# power_stage.net
KiCad netlist of a schematic drawn in EAGLE
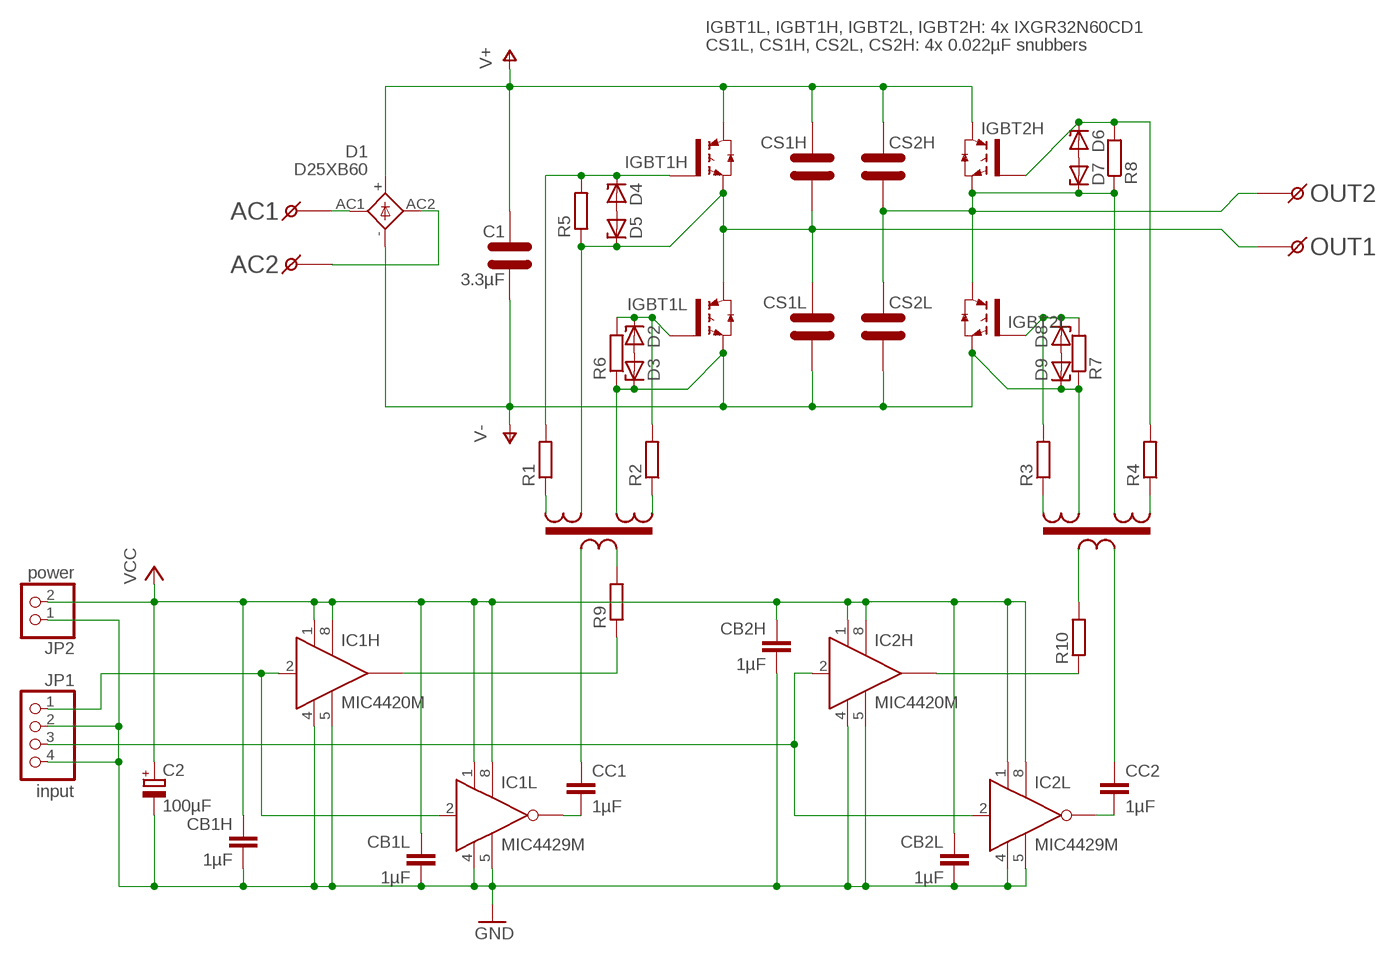
[diagram p0: schematic, sheet 1]

(export (version "E")
  (design (tool "Eeschema 10.0.6"))
  (components
    (comp (ref "C1")
      (value "3.3µF")
      (footprint "eagle-import:R75")
      (libsource (lib "eagle-import") (part "C_R75"))
    )
    (comp (ref "C2")
      (value "100µF")
      (footprint "eagle-import:E2,5-7")
      (libsource (lib "eagle-import") (part "CPOL-EUE2.5-7"))
    )
    (comp (ref "CB1H")
      (value "1µF")
      (footprint "eagle-import:C0805")
      (libsource (lib "eagle-import") (part "C-EUC0805"))
    )
    (comp (ref "CB1L")
      (value "1µF")
      (footprint "eagle-import:C0805")
      (libsource (lib "eagle-import") (part "C-EUC0805"))
    )
    (comp (ref "CB2H")
      (value "1µF")
      (footprint "eagle-import:C0805")
      (libsource (lib "eagle-import") (part "C-EUC0805"))
    )
    (comp (ref "CB2L")
      (value "1µF")
      (footprint "eagle-import:C0805")
      (libsource (lib "eagle-import") (part "C-EUC0805"))
    )
    (comp (ref "CC1")
      (value "1µF")
      (footprint "eagle-import:C0805")
      (libsource (lib "eagle-import") (part "C-EUC0805"))
    )
    (comp (ref "CC2")
      (value "1µF")
      (footprint "eagle-import:C0805")
      (libsource (lib "eagle-import") (part "C-EUC0805"))
    )
    (comp (ref "CS1H")
      (value "C_R76")
      (footprint "eagle-import:R76")
      (libsource (lib "eagle-import") (part "C_R76"))
    )
    (comp (ref "CS1L")
      (value "C_R76")
      (footprint "eagle-import:R76")
      (libsource (lib "eagle-import") (part "C_R76"))
    )
    (comp (ref "CS2H")
      (value "C_R76")
      (footprint "eagle-import:R76")
      (libsource (lib "eagle-import") (part "C_R76"))
    )
    (comp (ref "CS2L")
      (value "C_R76")
      (footprint "eagle-import:R76")
      (libsource (lib "eagle-import") (part "C_R76"))
    )
    (comp (ref "D1")
      (value "D25XB60")
      (footprint "eagle-import:D25XB60")
      (libsource (lib "eagle-import") (part "D25XB60"))
    )
    (comp (ref "D2")
      (value "ZENER-DIODESOD80C")
      (footprint "eagle-import:SOD80C")
      (libsource (lib "eagle-import") (part "ZENER-DIODESOD80C"))
    )
    (comp (ref "D3")
      (value "ZENER-DIODESOD80C")
      (footprint "eagle-import:SOD80C")
      (libsource (lib "eagle-import") (part "ZENER-DIODESOD80C"))
    )
    (comp (ref "D4")
      (value "ZENER-DIODESOD80C")
      (footprint "eagle-import:SOD80C")
      (libsource (lib "eagle-import") (part "ZENER-DIODESOD80C"))
    )
    (comp (ref "D5")
      (value "ZENER-DIODESOD80C")
      (footprint "eagle-import:SOD80C")
      (libsource (lib "eagle-import") (part "ZENER-DIODESOD80C"))
    )
    (comp (ref "D6")
      (value "ZENER-DIODESOD80C")
      (footprint "eagle-import:SOD80C")
      (libsource (lib "eagle-import") (part "ZENER-DIODESOD80C"))
    )
    (comp (ref "D7")
      (value "ZENER-DIODESOD80C")
      (footprint "eagle-import:SOD80C")
      (libsource (lib "eagle-import") (part "ZENER-DIODESOD80C"))
    )
    (comp (ref "D8")
      (value "ZENER-DIODESOD80C")
      (footprint "eagle-import:SOD80C")
      (libsource (lib "eagle-import") (part "ZENER-DIODESOD80C"))
    )
    (comp (ref "D9")
      (value "ZENER-DIODESOD80C")
      (footprint "eagle-import:SOD80C")
      (libsource (lib "eagle-import") (part "ZENER-DIODESOD80C"))
    )
    (comp (ref "GDT1")
      (value "GDT")
      (footprint "eagle-import:GDT")
      (libsource (lib "eagle-import") (part "GDT"))
    )
    (comp (ref "GDT2")
      (value "GDT")
      (footprint "eagle-import:GDT")
      (libsource (lib "eagle-import") (part "GDT"))
    )
    (comp (ref "IC1H")
      (value "MIC4420M")
      (footprint "eagle-import:SO-08")
      (libsource (lib "eagle-import") (part "MIC4420M"))
    )
    (comp (ref "IC1L")
      (value "MIC4429M")
      (footprint "eagle-import:SO-08")
      (libsource (lib "eagle-import") (part "MIC4429M"))
    )
    (comp (ref "IC2H")
      (value "MIC4420M")
      (footprint "eagle-import:SO-08")
      (libsource (lib "eagle-import") (part "MIC4420M"))
    )
    (comp (ref "IC2L")
      (value "MIC4429M")
      (footprint "eagle-import:SO-08")
      (libsource (lib "eagle-import") (part "MIC4429M"))
    )
    (comp (ref "IGBT1H")
      (value "IXGR32N60CD1")
      (footprint "eagle-import:TO-247AD-V")
      (libsource (lib "eagle-import") (part "IXGR32N60CD1"))
    )
    (comp (ref "IGBT1L")
      (value "IXGR32N60CD1")
      (footprint "eagle-import:TO-247AD-V")
      (libsource (lib "eagle-import") (part "IXGR32N60CD1"))
    )
    (comp (ref "IGBT2H")
      (value "IXGR32N60CD1")
      (footprint "eagle-import:TO-247AD-V")
      (libsource (lib "eagle-import") (part "IXGR32N60CD1"))
    )
    (comp (ref "IGBT2L")
      (value "IXGR32N60CD1")
      (footprint "eagle-import:TO-247AD-V")
      (libsource (lib "eagle-import") (part "IXGR32N60CD1"))
    )
    (comp (ref "J1")
      (value "AC1")
      (footprint "eagle-import:SCREW")
      (libsource (lib "eagle-import") (part "SCREW"))
    )
    (comp (ref "J2")
      (value "AC2")
      (footprint "eagle-import:SCREW")
      (libsource (lib "eagle-import") (part "SCREW"))
    )
    (comp (ref "J3")
      (value "OUT1")
      (footprint "eagle-import:SCREW")
      (libsource (lib "eagle-import") (part "SCREW"))
    )
    (comp (ref "J4")
      (value "OUT2")
      (footprint "eagle-import:SCREW")
      (libsource (lib "eagle-import") (part "SCREW"))
    )
    (comp (ref "JP1")
      (value "input")
      (footprint "eagle-import:1X04")
      (libsource (lib "eagle-import") (part "PINHD-1X4"))
    )
    (comp (ref "JP2")
      (value "power")
      (footprint "eagle-import:1X02")
      (libsource (lib "eagle-import") (part "PINHD-1X2"))
    )
    (comp (ref "R1")
      (value "R-EU_R0805")
      (footprint "eagle-import:R0805")
      (libsource (lib "eagle-import") (part "R-EU_R0805"))
    )
    (comp (ref "R2")
      (value "R-EU_R0805")
      (footprint "eagle-import:R0805")
      (libsource (lib "eagle-import") (part "R-EU_R0805"))
    )
    (comp (ref "R3")
      (value "R-EU_R0805")
      (footprint "eagle-import:R0805")
      (libsource (lib "eagle-import") (part "R-EU_R0805"))
    )
    (comp (ref "R4")
      (value "R-EU_R0805")
      (footprint "eagle-import:R0805")
      (libsource (lib "eagle-import") (part "R-EU_R0805"))
    )
    (comp (ref "R5")
      (value "R-EU_R0805")
      (footprint "eagle-import:R0805")
      (libsource (lib "eagle-import") (part "R-EU_R0805"))
    )
    (comp (ref "R6")
      (value "R-EU_R0805")
      (footprint "eagle-import:R0805")
      (libsource (lib "eagle-import") (part "R-EU_R0805"))
    )
    (comp (ref "R7")
      (value "R-EU_R0805")
      (footprint "eagle-import:R0805")
      (libsource (lib "eagle-import") (part "R-EU_R0805"))
    )
    (comp (ref "R8")
      (value "R-EU_R0805")
      (footprint "eagle-import:R0805")
      (libsource (lib "eagle-import") (part "R-EU_R0805"))
    )
    (comp (ref "R9")
      (value "R-EU_R0805")
      (footprint "eagle-import:R0805")
      (libsource (lib "eagle-import") (part "R-EU_R0805"))
    )
    (comp (ref "R10")
      (value "R-EU_R0805")
      (footprint "eagle-import:R0805")
      (libsource (lib "eagle-import") (part "R-EU_R0805"))
    )
  )
  (nets
    (net (code "1") (name "GND") (class "Default")
      (node (ref "C2") (pin "-") (pinfunction "-_-") (pintype "passive"))
      (node (ref "CB1H") (pin "2") (pinfunction "2_2") (pintype "passive"))
      (node (ref "CB1L") (pin "2") (pinfunction "2_2") (pintype "passive"))
      (node (ref "CB2H") (pin "2") (pinfunction "2_2") (pintype "passive"))
      (node (ref "CB2L") (pin "2") (pinfunction "2_2") (pintype "passive"))
      (node (ref "IC1H") (pin "4") (pinfunction "GND_4") (pintype "power_in"))
      (node (ref "IC1H") (pin "5") (pinfunction "GND1_5") (pintype "power_in"))
      (node (ref "IC1L") (pin "4") (pinfunction "GND_4") (pintype "power_in"))
      (node (ref "IC1L") (pin "5") (pinfunction "GND1_5") (pintype "power_in"))
      (node (ref "IC2H") (pin "4") (pinfunction "GND_4") (pintype "power_in"))
      (node (ref "IC2H") (pin "5") (pinfunction "GND1_5") (pintype "power_in"))
      (node (ref "IC2L") (pin "4") (pinfunction "GND_4") (pintype "power_in"))
      (node (ref "IC2L") (pin "5") (pinfunction "GND1_5") (pintype "power_in"))
      (node (ref "JP1") (pin "2") (pinfunction "2_2") (pintype "passive"))
      (node (ref "JP1") (pin "4") (pinfunction "4_4") (pintype "passive"))
      (node (ref "JP2") (pin "1") (pinfunction "1_1") (pintype "passive"))
    )
    (net (code "2") (name "Net-(CC1-Pad1)") (class "Default")
      (node (ref "CC1") (pin "1") (pinfunction "1_1") (pintype "passive"))
      (node (ref "GDT1") (pin "PA") (pinfunction "PA_PA") (pintype "passive"))
    )
    (net (code "3") (name "Net-(CC1-Pad2)") (class "Default")
      (node (ref "CC1") (pin "2") (pinfunction "2_2") (pintype "passive"))
      (node (ref "IC1L") (pin "6") (pinfunction "OUT_6") (pintype "passive"))
    )
    (net (code "4") (name "Net-(CC2-Pad1)") (class "Default")
      (node (ref "CC2") (pin "1") (pinfunction "1_1") (pintype "passive"))
      (node (ref "GDT2") (pin "PA") (pinfunction "PA_PA") (pintype "passive"))
    )
    (net (code "5") (name "Net-(CC2-Pad2)") (class "Default")
      (node (ref "CC2") (pin "2") (pinfunction "2_2") (pintype "passive"))
      (node (ref "IC2L") (pin "6") (pinfunction "OUT_6") (pintype "passive"))
    )
    (net (code "6") (name "Net-(D1-PadAC1)") (class "Default")
      (node (ref "D1") (pin "AC1") (pinfunction "AC1_AC1") (pintype "passive"))
      (node (ref "J1") (pin "P$1") (pinfunction "1_P$1") (pintype "bidirectional"))
      (node (ref "J1") (pin "P$2") (pinfunction "1_P$2") (pintype "bidirectional"))
      (node (ref "J1") (pin "P$3") (pinfunction "1_P$3") (pintype "bidirectional"))
      (node (ref "J1") (pin "P$4") (pinfunction "1_P$4") (pintype "bidirectional"))
    )
    (net (code "7") (name "Net-(D1-PadAC2)") (class "Default")
      (node (ref "D1") (pin "AC2") (pinfunction "AC2_AC2") (pintype "passive"))
      (node (ref "J2") (pin "P$1") (pinfunction "1_P$1") (pintype "bidirectional"))
      (node (ref "J2") (pin "P$2") (pinfunction "1_P$2") (pintype "bidirectional"))
      (node (ref "J2") (pin "P$3") (pinfunction "1_P$3") (pintype "bidirectional"))
      (node (ref "J2") (pin "P$4") (pinfunction "1_P$4") (pintype "bidirectional"))
    )
    (net (code "8") (name "Net-(D2-PadA)") (class "Default")
      (node (ref "D2") (pin "A") (pinfunction "A_A") (pintype "passive"))
      (node (ref "D3") (pin "A") (pinfunction "A_A") (pintype "passive"))
    )
    (net (code "9") (name "Net-(D2-PadC)") (class "Default")
      (node (ref "D2") (pin "C") (pinfunction "C_C") (pintype "passive"))
      (node (ref "IGBT1L") (pin "G") (pinfunction "G_G") (pintype "passive"))
      (node (ref "R2") (pin "2") (pinfunction "2_2") (pintype "passive"))
      (node (ref "R6") (pin "2") (pinfunction "2_2") (pintype "passive"))
    )
    (net (code "10") (name "Net-(D4-PadA)") (class "Default")
      (node (ref "D4") (pin "A") (pinfunction "A_A") (pintype "passive"))
      (node (ref "D5") (pin "A") (pinfunction "A_A") (pintype "passive"))
    )
    (net (code "11") (name "Net-(D4-PadC)") (class "Default")
      (node (ref "D4") (pin "C") (pinfunction "C_C") (pintype "passive"))
      (node (ref "IGBT1H") (pin "G") (pinfunction "G_G") (pintype "passive"))
      (node (ref "R1") (pin "2") (pinfunction "2_2") (pintype "passive"))
      (node (ref "R5") (pin "2") (pinfunction "2_2") (pintype "passive"))
    )
    (net (code "12") (name "Net-(D6-PadA)") (class "Default")
      (node (ref "D6") (pin "A") (pinfunction "A_A") (pintype "passive"))
      (node (ref "D7") (pin "A") (pinfunction "A_A") (pintype "passive"))
    )
    (net (code "13") (name "Net-(D6-PadC)") (class "Default")
      (node (ref "D6") (pin "C") (pinfunction "C_C") (pintype "passive"))
      (node (ref "IGBT2H") (pin "G") (pinfunction "G_G") (pintype "passive"))
      (node (ref "R4") (pin "2") (pinfunction "2_2") (pintype "passive"))
      (node (ref "R8") (pin "2") (pinfunction "2_2") (pintype "passive"))
    )
    (net (code "14") (name "Net-(D8-PadA)") (class "Default")
      (node (ref "D8") (pin "A") (pinfunction "A_A") (pintype "passive"))
      (node (ref "D9") (pin "A") (pinfunction "A_A") (pintype "passive"))
    )
    (net (code "15") (name "Net-(D8-PadC)") (class "Default")
      (node (ref "D8") (pin "C") (pinfunction "C_C") (pintype "passive"))
      (node (ref "IGBT2L") (pin "G") (pinfunction "G_G") (pintype "passive"))
      (node (ref "R3") (pin "2") (pinfunction "2_2") (pintype "passive"))
      (node (ref "R7") (pin "2") (pinfunction "2_2") (pintype "passive"))
    )
    (net (code "16") (name "Net-(GDT1-PadPB)") (class "Default")
      (node (ref "GDT1") (pin "PB") (pinfunction "PB_PB") (pintype "passive"))
      (node (ref "R9") (pin "2") (pinfunction "2_2") (pintype "passive"))
    )
    (net (code "17") (name "Net-(GDT1-PadS1A)") (class "Default")
      (node (ref "GDT1") (pin "S1A") (pinfunction "S1A_S1A") (pintype "passive"))
      (node (ref "R1") (pin "1") (pinfunction "1_1") (pintype "passive"))
    )
    (net (code "18") (name "Net-(GDT1-PadS2B)") (class "Default")
      (node (ref "GDT1") (pin "S2B") (pinfunction "S2B_S2B") (pintype "passive"))
      (node (ref "R2") (pin "1") (pinfunction "1_1") (pintype "passive"))
    )
    (net (code "19") (name "Net-(GDT2-PadPB)") (class "Default")
      (node (ref "GDT2") (pin "PB") (pinfunction "PB_PB") (pintype "passive"))
      (node (ref "R10") (pin "2") (pinfunction "2_2") (pintype "passive"))
    )
    (net (code "20") (name "Net-(GDT2-PadS1A)") (class "Default")
      (node (ref "GDT2") (pin "S1A") (pinfunction "S1A_S1A") (pintype "passive"))
      (node (ref "R4") (pin "1") (pinfunction "1_1") (pintype "passive"))
    )
    (net (code "21") (name "Net-(GDT2-PadS2B)") (class "Default")
      (node (ref "GDT2") (pin "S2B") (pinfunction "S2B_S2B") (pintype "passive"))
      (node (ref "R3") (pin "1") (pinfunction "1_1") (pintype "passive"))
    )
    (net (code "22") (name "Net-(IC1H-IN)") (class "Default")
      (node (ref "IC1H") (pin "2") (pinfunction "IN_2") (pintype "input"))
      (node (ref "IC1L") (pin "2") (pinfunction "IN_2") (pintype "input"))
      (node (ref "JP1") (pin "1") (pinfunction "1_1") (pintype "passive"))
    )
    (net (code "23") (name "Net-(IC1H-OUT-Pad6)") (class "Default")
      (node (ref "IC1H") (pin "6") (pinfunction "OUT_6") (pintype "passive"))
      (node (ref "R9") (pin "1") (pinfunction "1_1") (pintype "passive"))
    )
    (net (code "24") (name "Net-(IC2H-IN)") (class "Default")
      (node (ref "IC2H") (pin "2") (pinfunction "IN_2") (pintype "input"))
      (node (ref "IC2L") (pin "2") (pinfunction "IN_2") (pintype "input"))
      (node (ref "JP1") (pin "3") (pinfunction "3_3") (pintype "passive"))
    )
    (net (code "25") (name "Net-(IC2H-OUT-Pad6)") (class "Default")
      (node (ref "IC2H") (pin "6") (pinfunction "OUT_6") (pintype "passive"))
      (node (ref "R10") (pin "1") (pinfunction "1_1") (pintype "passive"))
    )
    (net (code "26") (name "Net-(IGBT1H-E)") (class "Default")
      (node (ref "CS1H") (pin "P$1") (pinfunction "P$1_P$1") (pintype "bidirectional"))
      (node (ref "CS1L") (pin "P$2") (pinfunction "P$2_P$2") (pintype "bidirectional"))
      (node (ref "D5") (pin "C") (pinfunction "C_C") (pintype "passive"))
      (node (ref "GDT1") (pin "S1B") (pinfunction "S1B_S1B") (pintype "passive"))
      (node (ref "IGBT1H") (pin "S") (pinfunction "E_S") (pintype "passive"))
      (node (ref "IGBT1L") (pin "D") (pinfunction "C_D") (pintype "passive"))
      (node (ref "J3") (pin "P$1") (pinfunction "1_P$1") (pintype "bidirectional"))
      (node (ref "J3") (pin "P$2") (pinfunction "1_P$2") (pintype "bidirectional"))
      (node (ref "J3") (pin "P$3") (pinfunction "1_P$3") (pintype "bidirectional"))
      (node (ref "J3") (pin "P$4") (pinfunction "1_P$4") (pintype "bidirectional"))
      (node (ref "R5") (pin "1") (pinfunction "1_1") (pintype "passive"))
    )
    (net (code "27") (name "Net-(IGBT2H-E)") (class "Default")
      (node (ref "CS2H") (pin "P$1") (pinfunction "P$1_P$1") (pintype "bidirectional"))
      (node (ref "CS2L") (pin "P$2") (pinfunction "P$2_P$2") (pintype "bidirectional"))
      (node (ref "D7") (pin "C") (pinfunction "C_C") (pintype "passive"))
      (node (ref "GDT2") (pin "S1B") (pinfunction "S1B_S1B") (pintype "passive"))
      (node (ref "IGBT2H") (pin "S") (pinfunction "E_S") (pintype "passive"))
      (node (ref "IGBT2L") (pin "D") (pinfunction "C_D") (pintype "passive"))
      (node (ref "J4") (pin "P$1") (pinfunction "1_P$1") (pintype "bidirectional"))
      (node (ref "J4") (pin "P$2") (pinfunction "1_P$2") (pintype "bidirectional"))
      (node (ref "J4") (pin "P$3") (pinfunction "1_P$3") (pintype "bidirectional"))
      (node (ref "J4") (pin "P$4") (pinfunction "1_P$4") (pintype "bidirectional"))
      (node (ref "R8") (pin "1") (pinfunction "1_1") (pintype "passive"))
    )
    (net (code "28") (name "V+") (class "Default")
      (node (ref "C1") (pin "P$2") (pinfunction "P$2_P$2") (pintype "bidirectional"))
      (node (ref "CS1H") (pin "P$2") (pinfunction "P$2_P$2") (pintype "bidirectional"))
      (node (ref "CS2H") (pin "P$2") (pinfunction "P$2_P$2") (pintype "bidirectional"))
      (node (ref "D1") (pin "+") (pinfunction "+_+") (pintype "passive"))
      (node (ref "IGBT1H") (pin "D") (pinfunction "C_D") (pintype "passive"))
      (node (ref "IGBT2H") (pin "D") (pinfunction "C_D") (pintype "passive"))
    )
    (net (code "29") (name "V-") (class "Default")
      (node (ref "C1") (pin "P$1") (pinfunction "P$1_P$1") (pintype "bidirectional"))
      (node (ref "CS1L") (pin "P$1") (pinfunction "P$1_P$1") (pintype "bidirectional"))
      (node (ref "CS2L") (pin "P$1") (pinfunction "P$1_P$1") (pintype "bidirectional"))
      (node (ref "D1") (pin "-") (pinfunction "-_-") (pintype "passive"))
      (node (ref "D3") (pin "C") (pinfunction "C_C") (pintype "passive"))
      (node (ref "D9") (pin "C") (pinfunction "C_C") (pintype "passive"))
      (node (ref "GDT1") (pin "S2A") (pinfunction "S2A_S2A") (pintype "passive"))
      (node (ref "GDT2") (pin "S2A") (pinfunction "S2A_S2A") (pintype "passive"))
      (node (ref "IGBT1L") (pin "S") (pinfunction "E_S") (pintype "passive"))
      (node (ref "IGBT2L") (pin "S") (pinfunction "E_S") (pintype "passive"))
      (node (ref "R6") (pin "1") (pinfunction "1_1") (pintype "passive"))
      (node (ref "R7") (pin "1") (pinfunction "1_1") (pintype "passive"))
    )
    (net (code "30") (name "VCC") (class "Default")
      (node (ref "C2") (pin "+") (pinfunction "+_+") (pintype "passive"))
      (node (ref "CB1H") (pin "1") (pinfunction "1_1") (pintype "passive"))
      (node (ref "CB1L") (pin "1") (pinfunction "1_1") (pintype "passive"))
      (node (ref "CB2H") (pin "1") (pinfunction "1_1") (pintype "passive"))
      (node (ref "CB2L") (pin "1") (pinfunction "1_1") (pintype "passive"))
      (node (ref "IC1H") (pin "1") (pinfunction "VS_1") (pintype "power_in"))
      (node (ref "IC1H") (pin "8") (pinfunction "VS1_8") (pintype "power_in"))
      (node (ref "IC1L") (pin "1") (pinfunction "VS_1") (pintype "power_in"))
      (node (ref "IC1L") (pin "8") (pinfunction "VS1_8") (pintype "power_in"))
      (node (ref "IC2H") (pin "1") (pinfunction "VS_1") (pintype "power_in"))
      (node (ref "IC2H") (pin "8") (pinfunction "VS1_8") (pintype "power_in"))
      (node (ref "IC2L") (pin "1") (pinfunction "VS_1") (pintype "power_in"))
      (node (ref "IC2L") (pin "8") (pinfunction "VS1_8") (pintype "power_in"))
      (node (ref "JP2") (pin "2") (pinfunction "2_2") (pintype "passive"))
    )
    (net (code "31") (name "unconnected-(IC1H-OUT-Pad7)") (class "Default")
      (node (ref "IC1H") (pin "7") (pinfunction "OUT_7") (pintype "passive"))
    )
    (net (code "32") (name "unconnected-(IC1L-OUT-Pad7)") (class "Default")
      (node (ref "IC1L") (pin "7") (pinfunction "OUT_7") (pintype "passive"))
    )
    (net (code "33") (name "unconnected-(IC2H-OUT-Pad7)") (class "Default")
      (node (ref "IC2H") (pin "7") (pinfunction "OUT_7") (pintype "passive"))
    )
    (net (code "34") (name "unconnected-(IC2L-OUT-Pad7)") (class "Default")
      (node (ref "IC2L") (pin "7") (pinfunction "OUT_7") (pintype "passive"))
    )
  )
)
